# ATC9213.net
KiCad netlist of a schematic drawn in Altium Designer
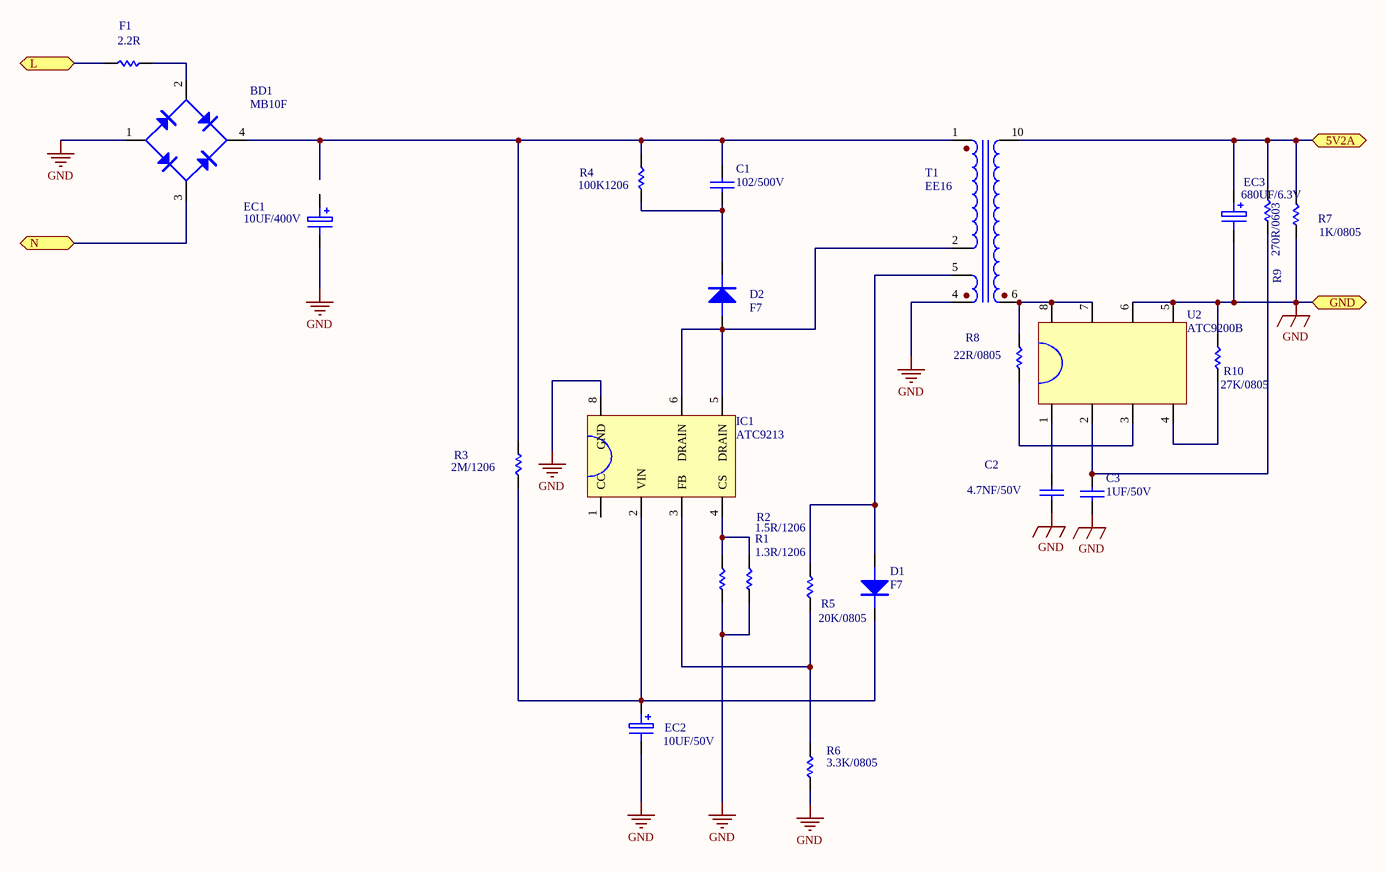
[diagram p0: ATC9213 原理图.SchDoc]

(export (version "E")
  (design (tool "Eeschema 10.0.6"))
  (components
    (comp (ref "BD1") (value "MB10F") (libsource (lib "二极管 三极管 MOS管") (part "BD")))
    (comp (ref "C1") (value "102/500V") (footprint "CC5") (libsource (lib "电阻 电容") (part "CC")))
    (comp (ref "C2") (value "4.7NF/50V") (footprint "CC5") (libsource (lib "电阻 电容") (part "CC")))
    (comp (ref "C3") (value "1UF/50V") (footprint "CC5") (libsource (lib "电阻 电容") (part "CC")))
    (comp (ref "D1") (value "F7") (footprint "DO-41A") (libsource (lib "二极管 三极管 MOS管") (part "D")))
    (comp (ref "D2") (value "F7") (footprint "DO-41A") (libsource (lib "二极管 三极管 MOS管") (part "D")))
    (comp (ref "EC1") (value "10UF/400V") (footprint "EC-8") (libsource (lib "电阻 电容") (part "CE")))
    (comp (ref "EC2") (value "10UF/50V") (footprint "EC-5") (libsource (lib "电阻 电容") (part "CE")))
    (comp (ref "EC3") (value "680UF/6.3V") (footprint "EC-6") (libsource (lib "电阻 电容") (part "CE")))
    (comp (ref "F1") (value "2.2R") (footprint "R1W") (libsource (lib "电阻 电容") (part "R")))
    (comp (ref "IC1") (value "ATC9213") (libsource (lib "IC ") (part "DIP8")))
    (comp (ref "R1") (value "1.3R/1206") (footprint "1206B") (libsource (lib "电阻 电容") (part "R")))
    (comp (ref "R2") (value "1.5R/1206") (footprint "1206B") (libsource (lib "电阻 电容") (part "R")))
    (comp (ref "R3") (value "2M/1206") (footprint "1206B") (libsource (lib "电阻 电容") (part "R")))
    (comp (ref "R4") (value "100K1206") (footprint "1206B") (libsource (lib "电阻 电容") (part "R")))
    (comp (ref "R5") (value "20K/0805") (footprint "0805B") (libsource (lib "电阻 电容") (part "R")))
    (comp (ref "R6") (value "3.3K/0805") (footprint "0805B") (libsource (lib "电阻 电容") (part "R")))
    (comp (ref "R7") (value "1K/0805") (footprint "0805B") (libsource (lib "电阻 电容") (part "R")))
    (comp (ref "R8") (value "22R/0805") (footprint "0805B") (libsource (lib "电阻 电容") (part "R")))
    (comp (ref "R9") (value "270R/0603") (footprint "0805B") (libsource (lib "电阻 电容") (part "R")))
    (comp (ref "R10") (value "27K/0805") (footprint "0805B") (libsource (lib "电阻 电容") (part "R")))
    (comp (ref "T1") (value "EE16") (footprint "EE13 4+4") (libsource (lib "变压器 电感") (part "EFD25")))
    (comp (ref "U2") (value "ATC9200B") (libsource (lib "") (part "DIP8_1")))
  )
  (nets
    (net (code "1") (name "/5V2A") (class "Default")
      (node (ref "EC3") (pin "1") (pinfunction "1_1") (pintype "passive"))
      (node (ref "R7") (pin "2") (pinfunction "2_2") (pintype "passive"))
      (node (ref "R9") (pin "2") (pinfunction "2_2") (pintype "passive"))
      (node (ref "T1") (pin "10") (pinfunction "F_10") (pintype "passive"))
    )
    (net (code "2") (name "/L") (class "Default")
      (node (ref "F1") (pin "2") (pinfunction "2_2") (pintype "passive"))
    )
    (net (code "3") (name "/N") (class "Default")
      (node (ref "BD1") (pin "3") (pinfunction "3_3") (pintype "passive"))
    )
    (net (code "4") (name "GND") (class "Default")
      (node (ref "BD1") (pin "1") (pinfunction "V-_1") (pintype "passive"))
      (node (ref "C2") (pin "2") (pinfunction "2_2") (pintype "passive"))
      (node (ref "C3") (pin "2") (pinfunction "2_2") (pintype "passive"))
      (node (ref "EC1") (pin "2") (pinfunction "2_2") (pintype "passive"))
      (node (ref "EC2") (pin "2") (pinfunction "2_2") (pintype "passive"))
      (node (ref "EC3") (pin "2") (pinfunction "2_2") (pintype "passive"))
      (node (ref "IC1") (pin "8") (pinfunction "GND_8") (pintype "passive"))
      (node (ref "R1") (pin "1") (pinfunction "1_1") (pintype "passive"))
      (node (ref "R10") (pin "2") (pinfunction "2_2") (pintype "passive"))
      (node (ref "R2") (pin "1") (pinfunction "1_1") (pintype "passive"))
      (node (ref "R6") (pin "1") (pinfunction "1_1") (pintype "passive"))
      (node (ref "R7") (pin "1") (pinfunction "1_1") (pintype "passive"))
      (node (ref "T1") (pin "4") (pinfunction "4_4") (pintype "passive"))
      (node (ref "U2") (pin "5") (pintype "passive"))
      (node (ref "U2") (pin "6") (pintype "passive"))
    )
    (net (code "5") (name "Net-(BD1-Pad2)") (class "Default")
      (node (ref "BD1") (pin "2") (pinfunction "2_2") (pintype "passive"))
      (node (ref "F1") (pin "1") (pinfunction "1_1") (pintype "passive"))
    )
    (net (code "6") (name "Net-(BD1-V+)") (class "Default")
      (node (ref "BD1") (pin "4") (pinfunction "V+_4") (pintype "passive"))
      (node (ref "C1") (pin "1") (pinfunction "1_1") (pintype "passive"))
      (node (ref "R3") (pin "1") (pinfunction "1_1") (pintype "passive"))
      (node (ref "R4") (pin "2") (pinfunction "2_2") (pintype "passive"))
      (node (ref "T1") (pin "1") (pinfunction "1_1") (pintype "passive"))
    )
    (net (code "7") (name "Net-(C2-Pad1)") (class "Default")
      (node (ref "C2") (pin "1") (pinfunction "1_1") (pintype "passive"))
      (node (ref "U2") (pin "1") (pintype "passive"))
    )
    (net (code "8") (name "Net-(C3-Pad1)") (class "Default")
      (node (ref "C3") (pin "1") (pinfunction "1_1") (pintype "passive"))
      (node (ref "R9") (pin "1") (pinfunction "1_1") (pintype "passive"))
      (node (ref "U2") (pin "2") (pintype "passive"))
    )
    (net (code "9") (name "Net-(D1-A)") (class "Default")
      (node (ref "D1") (pin "1") (pinfunction "A_1") (pintype "passive"))
      (node (ref "R5") (pin "1") (pinfunction "1_1") (pintype "passive"))
      (node (ref "T1") (pin "5") (pinfunction "5_5") (pintype "passive"))
    )
    (net (code "10") (name "Net-(D1-K)") (class "Default")
      (node (ref "D1") (pin "2") (pinfunction "K_2") (pintype "passive"))
      (node (ref "EC2") (pin "1") (pinfunction "1_1") (pintype "passive"))
      (node (ref "IC1") (pin "2") (pinfunction "VIN_2") (pintype "passive"))
      (node (ref "R3") (pin "2") (pinfunction "2_2") (pintype "passive"))
    )
    (net (code "11") (name "Net-(D2-A)") (class "Default")
      (node (ref "D2") (pin "1") (pinfunction "A_1") (pintype "passive"))
      (node (ref "IC1") (pin "5") (pinfunction "DRAIN_5") (pintype "passive"))
      (node (ref "IC1") (pin "6") (pinfunction "DRAIN_6") (pintype "passive"))
      (node (ref "T1") (pin "2") (pinfunction "2_2") (pintype "passive"))
    )
    (net (code "12") (name "Net-(D2-K)") (class "Default")
      (node (ref "C1") (pin "2") (pinfunction "2_2") (pintype "passive"))
      (node (ref "D2") (pin "2") (pinfunction "K_2") (pintype "passive"))
      (node (ref "R4") (pin "1") (pinfunction "1_1") (pintype "passive"))
    )
    (net (code "13") (name "Net-(IC1-CS)") (class "Default")
      (node (ref "IC1") (pin "4") (pinfunction "CS_4") (pintype "passive"))
      (node (ref "R1") (pin "2") (pinfunction "2_2") (pintype "passive"))
      (node (ref "R2") (pin "2") (pinfunction "2_2") (pintype "passive"))
    )
    (net (code "14") (name "Net-(IC1-FB)") (class "Default")
      (node (ref "IC1") (pin "3") (pinfunction "FB_3") (pintype "passive"))
      (node (ref "R5") (pin "2") (pinfunction "2_2") (pintype "passive"))
      (node (ref "R6") (pin "2") (pinfunction "2_2") (pintype "passive"))
    )
    (net (code "15") (name "Net-(R8-Pad1)") (class "Default")
      (node (ref "R8") (pin "1") (pinfunction "1_1") (pintype "passive"))
      (node (ref "U2") (pin "3") (pintype "passive"))
    )
    (net (code "16") (name "Net-(R10-Pad1)") (class "Default")
      (node (ref "R10") (pin "1") (pinfunction "1_1") (pintype "passive"))
      (node (ref "U2") (pin "4") (pintype "passive"))
    )
    (net (code "17") (name "Net-(T1-S)") (class "Default")
      (node (ref "R8") (pin "2") (pinfunction "2_2") (pintype "passive"))
      (node (ref "T1") (pin "6") (pinfunction "S_6") (pintype "passive"))
      (node (ref "U2") (pin "7") (pintype "passive"))
      (node (ref "U2") (pin "8") (pintype "passive"))
    )
    (net (code "18") (name "unconnected-(EC1-Pad1)") (class "Default")
      (node (ref "EC1") (pin "1") (pinfunction "1_1") (pintype "passive"))
    )
    (net (code "19") (name "unconnected-(IC1-CC-Pad1)") (class "Default")
      (node (ref "IC1") (pin "1") (pinfunction "CC_1") (pintype "passive"))
    )
  )
)
